# PiezoPreamp_V5.net
KiCad netlist of a schematic drawn in EAGLE
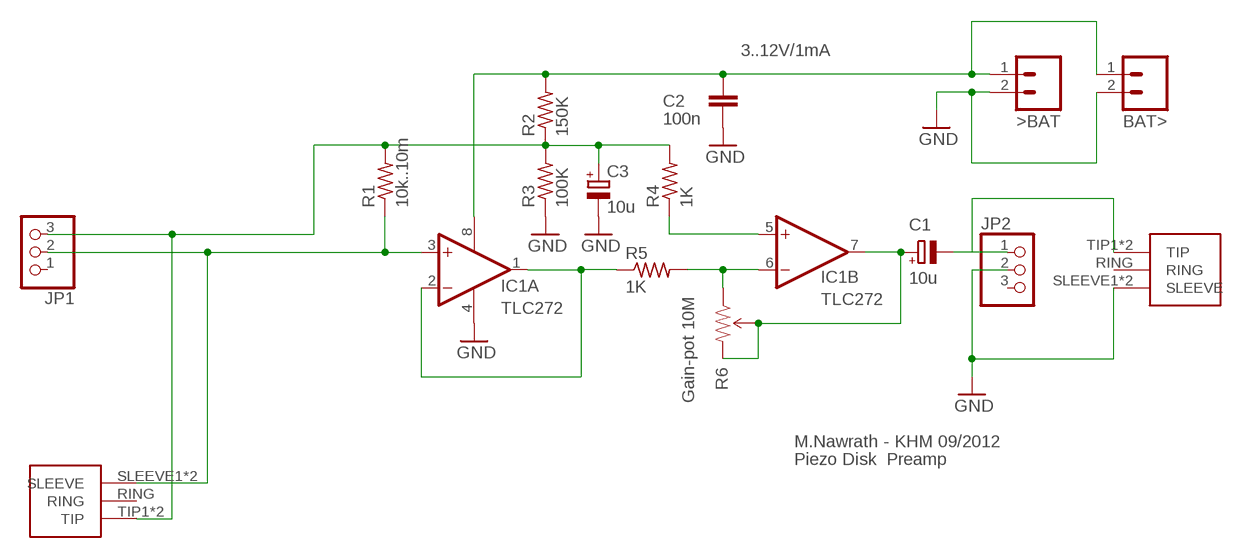
[diagram p0: schematic, sheet 1]

(export (version "E")
  (design (tool "Eeschema 10.0.6"))
  (components
    (comp (ref ">BAT")
      (value "M02LOCK")
      (footprint "eagle-import:1X02_LOCK")
      (libsource (lib "eagle-import") (part "M02LOCK"))
    )
    (comp (ref "BAT>")
      (value "M02LOCK")
      (footprint "eagle-import:1X02_LOCK")
      (libsource (lib "eagle-import") (part "M02LOCK"))
    )
    (comp (ref "C1")
      (value "10u")
      (footprint "eagle-import:E2,5-5")
      (libsource (lib "eagle-import") (part "CPOL-EUE2.5-5"))
    )
    (comp (ref "C2")
      (value "100n")
      (footprint "eagle-import:C025-025X050")
      (libsource (lib "eagle-import") (part "C-EU025-025X050"))
    )
    (comp (ref "C3")
      (value "10u")
      (footprint "eagle-import:E2,5-5")
      (libsource (lib "eagle-import") (part "CPOL-EUE2.5-5"))
    )
    (comp (ref "IC1")
      (value "TLC272")
      (footprint "eagle-import:DIL08")
      (libsource (lib "eagle-import") (part "TLC272P"))
    )
    (comp (ref "JP1")
      (value "PINHD-1X3")
      (footprint "eagle-import:1X03")
      (libsource (lib "eagle-import") (part "PINHD-1X3"))
    )
    (comp (ref "JP2")
      (value "PINHD-1X3")
      (footprint "eagle-import:1X03")
      (libsource (lib "eagle-import") (part "PINHD-1X3"))
    )
    (comp (ref "OUT1-TRS")
      (value "1/8\"-F-STEREO-PCB")
      (footprint "eagle-import:1_8_-F-STEREO-PCB")
      (libsource (lib "eagle-import") (part "1/8{dblquote}-F-STEREO-PCB"))
    )
    (comp (ref "R1")
      (value "10k..10m")
      (footprint "eagle-import:0204V")
      (libsource (lib "eagle-import") (part "R-US_0204/2V"))
    )
    (comp (ref "R2")
      (value "150K")
      (footprint "eagle-import:0204V")
      (libsource (lib "eagle-import") (part "R-US_0204/2V"))
    )
    (comp (ref "R3")
      (value "100K")
      (footprint "eagle-import:0204V")
      (libsource (lib "eagle-import") (part "R-US_0204/2V"))
    )
    (comp (ref "R4")
      (value "1K")
      (footprint "eagle-import:0204V")
      (libsource (lib "eagle-import") (part "R-US_0204/2V"))
    )
    (comp (ref "R5")
      (value "1K")
      (footprint "eagle-import:0204V")
      (libsource (lib "eagle-import") (part "R-US_0204/2V"))
    )
    (comp (ref "R6")
      (value "Gain-pot 10M")
      (footprint "eagle-import:3386U")
      (libsource (lib "eagle-import") (part "TRIMPOT-PTH-KNOB"))
    )
    (comp (ref "U$2")
      (value "1/8\"-F-STEREO-PCB")
      (footprint "eagle-import:1_8_-F-STEREO-PCB")
      (libsource (lib "eagle-import") (part "1/8{dblquote}-F-STEREO-PCB"))
    )
  )
  (nets
    (net (code "1") (name "GND") (class "Default")
      (node (ref ">BAT") (pin "2") (pinfunction "2_2") (pintype "passive"))
      (node (ref "BAT>") (pin "2") (pinfunction "2_2") (pintype "passive"))
      (node (ref "C2") (pin "1") (pinfunction "1_1") (pintype "passive"))
      (node (ref "C3") (pin "-") (pinfunction "-_-") (pintype "passive"))
      (node (ref "IC1") (pin "4") (pinfunction "V-_4") (pintype "power_in"))
      (node (ref "JP2") (pin "2") (pinfunction "2_2") (pintype "passive"))
      (node (ref "OUT1-TRS") (pin "SLEEVE1") (pinfunction "SLEEVE_SLEEVE1") (pintype "bidirectional"))
      (node (ref "OUT1-TRS") (pin "SLEEVE2") (pinfunction "SLEEVE_SLEEVE2") (pintype "bidirectional"))
      (node (ref "R3") (pin "1") (pinfunction "1_1") (pintype "passive"))
    )
    (net (code "2") (name "Net-(C1-Pad-)") (class "Default")
      (node (ref "C1") (pin "-") (pinfunction "-_-") (pintype "passive"))
      (node (ref "JP2") (pin "1") (pinfunction "1_1") (pintype "passive"))
      (node (ref "OUT1-TRS") (pin "TIP1") (pinfunction "TIP_TIP1") (pintype "bidirectional"))
      (node (ref "OUT1-TRS") (pin "TIP2") (pinfunction "TIP_TIP2") (pintype "bidirectional"))
    )
    (net (code "3") (name "Net-(C3-Pad+)") (class "Default")
      (node (ref "C3") (pin "+") (pinfunction "+_+") (pintype "passive"))
      (node (ref "JP1") (pin "3") (pinfunction "3_3") (pintype "passive"))
      (node (ref "R1") (pin "2") (pinfunction "2_2") (pintype "passive"))
      (node (ref "R2") (pin "1") (pinfunction "1_1") (pintype "passive"))
      (node (ref "R3") (pin "2") (pinfunction "2_2") (pintype "passive"))
      (node (ref "R4") (pin "2") (pinfunction "2_2") (pintype "passive"))
      (node (ref "U$2") (pin "TIP1") (pinfunction "TIP_TIP1") (pintype "bidirectional"))
      (node (ref "U$2") (pin "TIP2") (pinfunction "TIP_TIP2") (pintype "bidirectional"))
    )
    (net (code "4") (name "Net-(IC1A-+IN)") (class "Default")
      (node (ref "IC1") (pin "3") (pinfunction "+IN_3") (pintype "input"))
      (node (ref "JP1") (pin "2") (pinfunction "2_2") (pintype "passive"))
      (node (ref "R1") (pin "1") (pinfunction "1_1") (pintype "passive"))
      (node (ref "U$2") (pin "SLEEVE1") (pinfunction "SLEEVE_SLEEVE1") (pintype "bidirectional"))
      (node (ref "U$2") (pin "SLEEVE2") (pinfunction "SLEEVE_SLEEVE2") (pintype "bidirectional"))
    )
    (net (code "5") (name "Net-(IC1A--IN)") (class "Default")
      (node (ref "IC1") (pin "1") (pinfunction "OUT_1") (pintype "output"))
      (node (ref "IC1") (pin "2") (pinfunction "-IN_2") (pintype "input"))
      (node (ref "R5") (pin "1") (pinfunction "1_1") (pintype "passive"))
    )
    (net (code "6") (name "Net-(IC1B-+IN)") (class "Default")
      (node (ref "IC1") (pin "5") (pinfunction "+IN_5") (pintype "input"))
      (node (ref "R4") (pin "1") (pinfunction "1_1") (pintype "passive"))
    )
    (net (code "7") (name "Net-(IC1B--IN)") (class "Default")
      (node (ref "IC1") (pin "6") (pinfunction "-IN_6") (pintype "input"))
      (node (ref "R5") (pin "2") (pinfunction "2_2") (pintype "passive"))
      (node (ref "R6") (pin "1") (pinfunction "CCW_1") (pintype "passive"))
    )
    (net (code "8") (name "Net-(IC1B-OUT)") (class "Default")
      (node (ref "C1") (pin "+") (pinfunction "+_+") (pintype "passive"))
      (node (ref "IC1") (pin "7") (pinfunction "OUT_7") (pintype "output"))
      (node (ref "R6") (pin "2") (pinfunction "WIPER_2") (pintype "passive"))
      (node (ref "R6") (pin "3") (pinfunction "CW_3") (pintype "passive"))
    )
    (net (code "9") (name "Net-(IC1C-V+)") (class "Default")
      (node (ref ">BAT") (pin "1") (pinfunction "1_1") (pintype "passive"))
      (node (ref "BAT>") (pin "1") (pinfunction "1_1") (pintype "passive"))
      (node (ref "C2") (pin "2") (pinfunction "2_2") (pintype "passive"))
      (node (ref "IC1") (pin "8") (pinfunction "V+_8") (pintype "power_in"))
      (node (ref "R2") (pin "2") (pinfunction "2_2") (pintype "passive"))
    )
    (net (code "10") (name "unconnected-(JP1-Pad1)") (class "Default")
      (node (ref "JP1") (pin "1") (pinfunction "1_1") (pintype "passive"))
    )
    (net (code "11") (name "unconnected-(JP2-Pad3)") (class "Default")
      (node (ref "JP2") (pin "3") (pinfunction "3_3") (pintype "passive"))
    )
    (net (code "12") (name "unconnected-(OUT1-TRS-PadRING)") (class "Default")
      (node (ref "OUT1-TRS") (pin "RING") (pinfunction "RING_RING") (pintype "bidirectional"))
    )
    (net (code "13") (name "unconnected-(U$2-PadRING)") (class "Default")
      (node (ref "U$2") (pin "RING") (pinfunction "RING_RING") (pintype "bidirectional"))
    )
  )
)
